# Altium_Simulation.net
KiCad netlist of a schematic drawn in Altium Designer
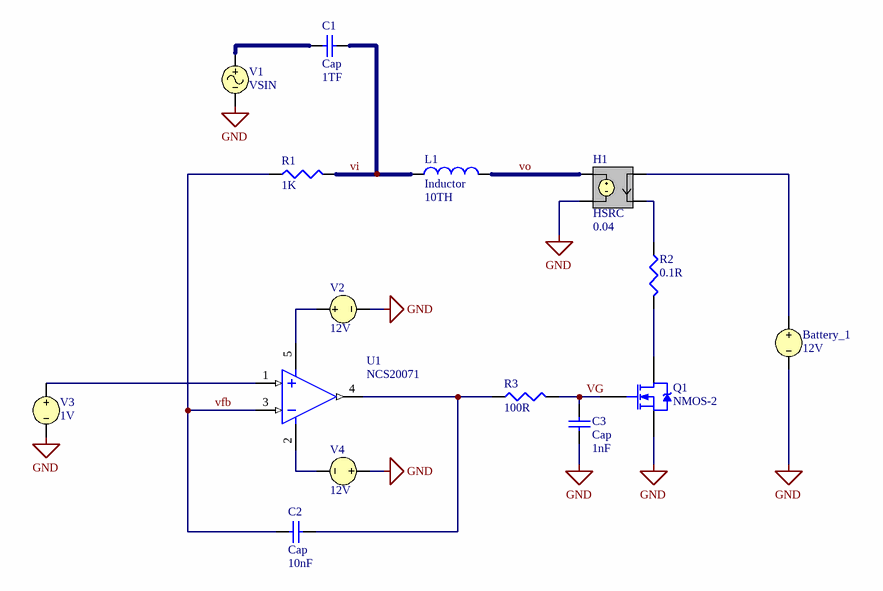
[diagram p0: Altium Simulation.SchDoc]

(export (version "E")
  (design (tool "Eeschema 10.0.6"))
  (components
    (comp (ref "Battery_1")
      (value "12V")
      (description "Voltage Source")
      (fields (field (name "PUBLISHER") "Altium Limited"))
      (libsource (lib "Simulation Sources") (part "VSRC"))
    )
    (comp (ref "C1")
      (value "Cap")
      (footprint "RAD-0.3")
      (description "Capacitor")
      (fields (field (name "ALTIUM_VALUE") "1TF") (field (name "PUBLISHER") "Altium Limited"))
      (libsource (lib "Miscellaneous Devices") (part "Cap"))
    )
    (comp (ref "C2")
      (value "Cap")
      (footprint "RAD-0.3")
      (description "Capacitor")
      (fields (field (name "ALTIUM_VALUE") "10nF") (field (name "PUBLISHER") "Altium Limited"))
      (libsource (lib "Miscellaneous Devices") (part "Cap"))
    )
    (comp (ref "C3")
      (value "Cap")
      (footprint "RAD-0.3")
      (description "Capacitor")
      (fields (field (name "ALTIUM_VALUE") "1nF") (field (name "PUBLISHER") "Altium Limited"))
      (libsource (lib "Miscellaneous Devices") (part "Cap"))
    )
    (comp (ref "H1")
      (value "HSRC")
      (description "Current Controlled Voltage Source")
      (fields (field (name "GAIN") "0.04") (field (name "PUBLISHER") "Altium Limited"))
      (libsource (lib "Simulation Sources") (part "HSRC"))
    )
    (comp (ref "L1")
      (value "Inductor")
      (footprint "0402-A")
      (fields (field (name "ALTIUM_VALUE") "10TH") (field (name "PUBLISHER") "Altium Limited"))
      (libsource (lib "Miscellaneous Devices") (part "Inductor"))
    )
    (comp (ref "Q1")
      (value "NMOS-2")
      (footprint "TO-220AB")
      (description "N-Channel Power MOSFET")
      (fields (field (name "PUBLISHER") "Altium Limited"))
      (libsource (lib "Miscellaneous Devices") (part "NMOS-2"))
    )
    (comp (ref "R1")
      (value "1K")
      (footprint "J1-0603")
      (description "Resistor")
      (fields (field (name "PUBLISHER") "Altium Limited"))
      (libsource (lib "Miscellaneous Devices") (part "Res3"))
    )
    (comp (ref "R2")
      (value "0.1R")
      (footprint "J1-0603")
      (description "Resistor")
      (fields (field (name "PUBLISHER") "Altium Limited"))
      (libsource (lib "Miscellaneous Devices") (part "Res3"))
    )
    (comp (ref "R3")
      (value "100R")
      (footprint "J1-0603")
      (description "Resistor")
      (fields (field (name "PUBLISHER") "Altium Limited"))
      (libsource (lib "Miscellaneous Devices") (part "Res3"))
    )
    (comp (ref "U1")
      (value "NCS20071")
      (footprint "SOT-553-5")
      (description "Rail-to-Rail Input/Output, 3 MHz Op Amps")
      (fields
        (field (name "1 SUPPLIER PART NUMBER") "MCP6021-E/SN-ND")
        (field (name "MANUFACTURER") "Microchip Technology")
      )
      (libsource (lib "Library_20-02-20") (part "NCS20071"))
    )
    (comp (ref "V1")
      (value "VSIN")
      (description "Sinusoidal Voltage Source")
      (fields (field (name "PUBLISHER") "Altium Limited"))
      (libsource (lib "Simulation Sources") (part "VSIN"))
    )
    (comp (ref "V2")
      (value "12V")
      (description "Voltage Source")
      (fields (field (name "PUBLISHER") "Altium Limited"))
      (libsource (lib "Simulation Sources") (part "VSRC"))
    )
    (comp (ref "V3")
      (value "1V")
      (description "Voltage Source")
      (fields (field (name "PUBLISHER") "Altium Limited"))
      (libsource (lib "Simulation Sources") (part "VSRC"))
    )
    (comp (ref "V4")
      (value "12V")
      (description "Voltage Source")
      (fields (field (name "PUBLISHER") "Altium Limited"))
      (libsource (lib "Simulation Sources") (part "VSRC"))
    )
  )
  (nets
    (net (code "1") (name "/VG") (class "Default")
      (node (ref "C3") (pin "2") (pinfunction "2_2") (pintype "passive"))
      (node (ref "Q1") (pin "1") (pinfunction "G_1") (pintype "passive"))
      (node (ref "R3") (pin "2") (pinfunction "2_2") (pintype "passive"))
    )
    (net (code "2") (name "/vfb") (class "Default")
      (node (ref "C2") (pin "1") (pinfunction "1_1") (pintype "passive"))
      (node (ref "R1") (pin "1") (pinfunction "1_1") (pintype "passive"))
      (node (ref "U1") (pin "3") (pintype "input"))
    )
    (net (code "3") (name "/vi") (class "Default")
      (node (ref "C1") (pin "1") (pinfunction "1_1") (pintype "passive"))
      (node (ref "L1") (pin "1") (pinfunction "1_1") (pintype "passive"))
      (node (ref "R1") (pin "2") (pinfunction "2_2") (pintype "passive"))
    )
    (net (code "4") (name "/vo") (class "Default")
      (node (ref "H1") (pin "3") (pinfunction "N+_3") (pintype "passive"))
      (node (ref "L1") (pin "2") (pinfunction "2_2") (pintype "passive"))
    )
    (net (code "5") (name "GND") (class "Default")
      (node (ref "Battery_1") (pin "2") (pinfunction "2_2") (pintype "passive"))
      (node (ref "C3") (pin "1") (pinfunction "1_1") (pintype "passive"))
      (node (ref "H1") (pin "4") (pinfunction "N-_4") (pintype "passive"))
      (node (ref "Q1") (pin "3") (pinfunction "S_3") (pintype "passive"))
      (node (ref "V1") (pin "2") (pinfunction "2_2") (pintype "passive"))
      (node (ref "V2") (pin "2") (pinfunction "2_2") (pintype "passive"))
      (node (ref "V3") (pin "2") (pinfunction "2_2") (pintype "passive"))
      (node (ref "V4") (pin "1") (pinfunction "1_1") (pintype "passive"))
    )
    (net (code "6") (name "Net-(C1-Pad2)") (class "Default")
      (node (ref "C1") (pin "2") (pinfunction "2_2") (pintype "passive"))
      (node (ref "V1") (pin "1") (pinfunction "1_1") (pintype "passive"))
    )
    (net (code "7") (name "Net-(C2-Pad2)") (class "Default")
      (node (ref "C2") (pin "2") (pinfunction "2_2") (pintype "passive"))
      (node (ref "R3") (pin "1") (pinfunction "1_1") (pintype "passive"))
      (node (ref "U1") (pin "4") (pintype "output"))
    )
    (net (code "8") (name "Net-(H1-NC+)") (class "Default")
      (node (ref "Battery_1") (pin "1") (pinfunction "1_1") (pintype "passive"))
      (node (ref "H1") (pin "1") (pinfunction "NC+_1") (pintype "passive"))
    )
    (net (code "9") (name "Net-(H1-NC-)") (class "Default")
      (node (ref "H1") (pin "2") (pinfunction "NC-_2") (pintype "passive"))
      (node (ref "R2") (pin "1") (pinfunction "1_1") (pintype "passive"))
    )
    (net (code "10") (name "Net-(Q1-D)") (class "Default")
      (node (ref "Q1") (pin "2") (pinfunction "D_2") (pintype "passive"))
      (node (ref "R2") (pin "2") (pinfunction "2_2") (pintype "passive"))
    )
    (net (code "11") (name "Net-(U1-Pad1)") (class "Default")
      (node (ref "U1") (pin "1") (pintype "input"))
      (node (ref "V3") (pin "1") (pinfunction "1_1") (pintype "passive"))
    )
    (net (code "12") (name "Net-(U1-Pad2)") (class "Default")
      (node (ref "U1") (pin "2") (pintype "power_in"))
      (node (ref "V4") (pin "2") (pinfunction "2_2") (pintype "passive"))
    )
    (net (code "13") (name "Net-(U1-Pad5)") (class "Default")
      (node (ref "U1") (pin "5") (pintype "power_in"))
      (node (ref "V2") (pin "1") (pinfunction "1_1") (pintype "passive"))
    )
  )
)
